# Sheet2.net
KiCad netlist of a schematic drawn in Altium Designer
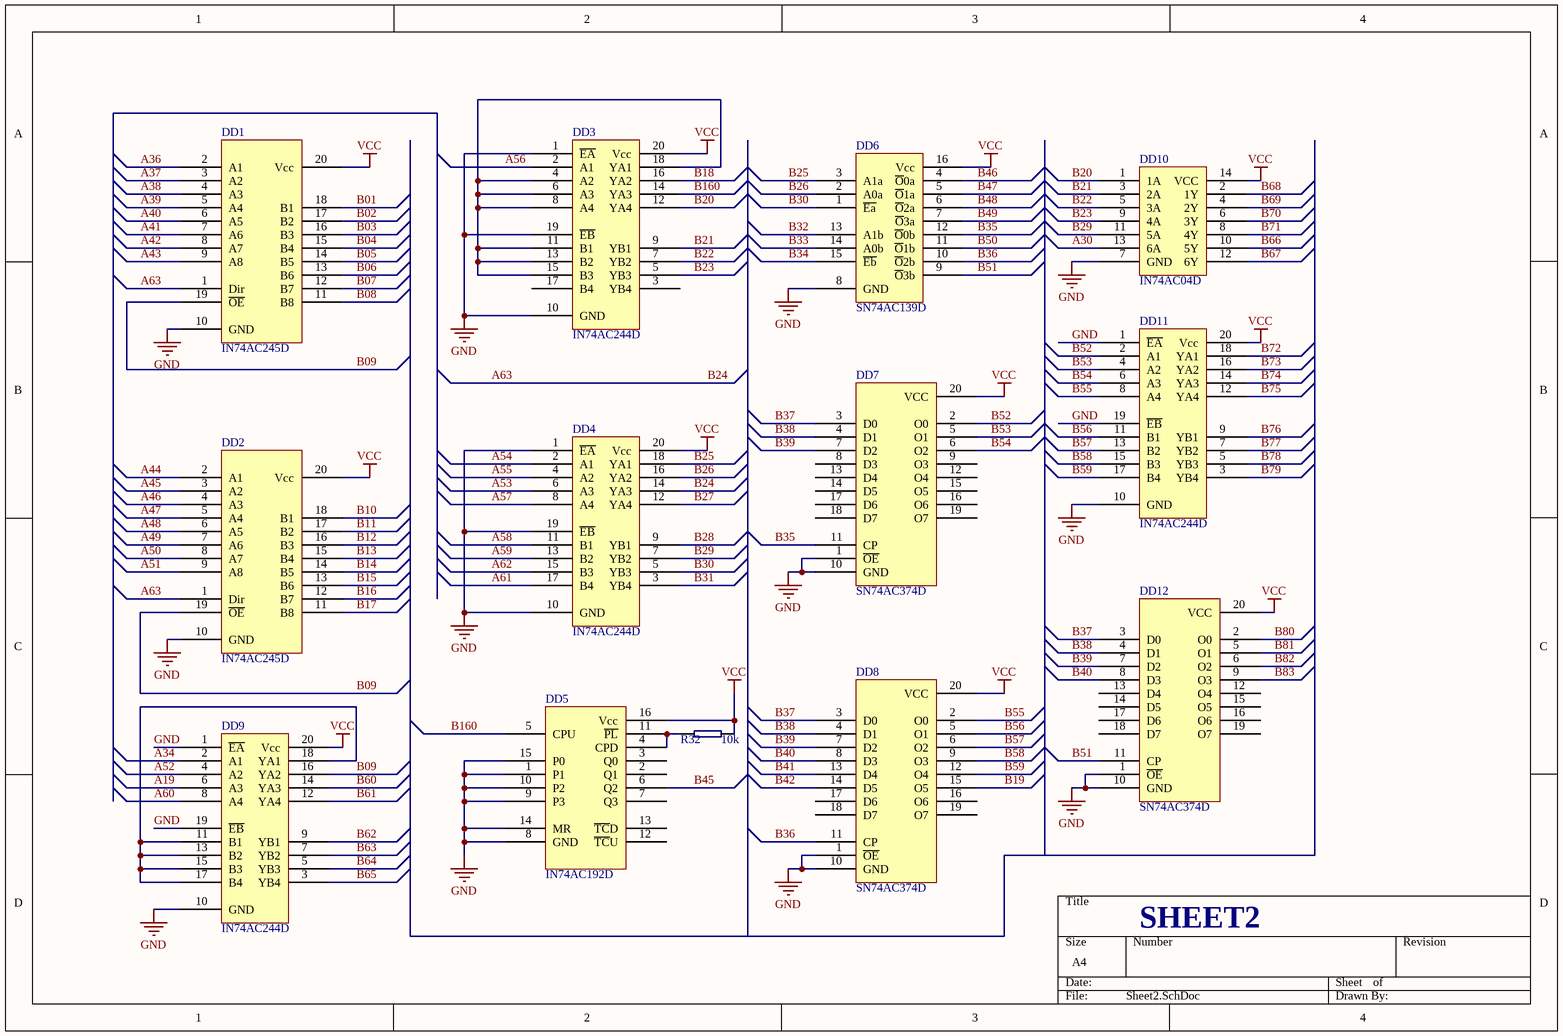
[diagram p0: Sheet2.SchDoc]

(export (version "E")
  (design (tool "Eeschema 10.0.6"))
  (components
    (comp (ref "DD1")
      (value "IN74AC245D")
      (footprint "20 SSOP-4.4")
      (libsource (lib "Board2") (part "IN74AC245D"))
    )
    (comp (ref "DD2")
      (value "IN74AC245D")
      (footprint "20 SSOP-4.4")
      (libsource (lib "Board2") (part "IN74AC245D"))
    )
    (comp (ref "DD3")
      (value "IN74AC244D")
      (footprint "20 SOIC-7.5")
      (libsource (lib "Board2") (part "IN74AC244D"))
    )
    (comp (ref "DD4")
      (value "IN74AC244D")
      (footprint "20 SOIC-7.5")
      (libsource (lib "Board2") (part "IN74AC244D"))
    )
    (comp (ref "DD5")
      (value "IN74AC192D")
      (footprint "16 SOIC-3.9")
      (libsource (lib "Board2") (part "IN74AC192D"))
    )
    (comp (ref "DD6")
      (value "SN74AC139D")
      (footprint "16 SOIC-3.9")
      (libsource (lib "Board2") (part "SN74AC139D"))
    )
    (comp (ref "DD7")
      (value "SN74AC374D")
      (footprint "20 SOIC-7.5")
      (libsource (lib "Board2") (part "SN74AC374D"))
    )
    (comp (ref "DD8")
      (value "SN74AC374D")
      (footprint "20 SOIC-7.5")
      (libsource (lib "Board2") (part "SN74AC374D"))
    )
    (comp (ref "DD9")
      (value "IN74AC244D")
      (footprint "20 SOIC-7.5")
      (libsource (lib "Board2") (part "IN74AC244D"))
    )
    (comp (ref "DD10")
      (value "IN74AC04D")
      (footprint "14 SOIC-3.9")
      (libsource (lib "Board2") (part "IN74AC04D"))
    )
    (comp (ref "DD11")
      (value "IN74AC244D")
      (footprint "20 SOIC-7.5")
      (libsource (lib "Board2") (part "IN74AC244D"))
    )
    (comp (ref "DD12")
      (value "SN74AC374D")
      (footprint "20 SOIC-7.5")
      (libsource (lib "*") (part "SN74AC374D"))
    )
    (comp (ref "R32")
      (value "10k")
      (footprint "0805")
      (fields (field (name "Comment") "R"))
      (libsource (lib "Board2") (part "R"))
    )
  )
  (nets
    (net (code "1") (name "/A19") (class "Default")
      (node (ref "DD9") (pin "6") (pinfunction "A3_6") (pintype "passive"))
    )
    (net (code "2") (name "/A30") (class "Default")
      (node (ref "DD10") (pin "13") (pinfunction "6A_13") (pintype "passive"))
    )
    (net (code "3") (name "/A34") (class "Default")
      (node (ref "DD9") (pin "2") (pinfunction "A1_2") (pintype "passive"))
    )
    (net (code "4") (name "/A36") (class "Default")
      (node (ref "DD1") (pin "2") (pinfunction "A1_2") (pintype "passive"))
    )
    (net (code "5") (name "/A37") (class "Default")
      (node (ref "DD1") (pin "3") (pinfunction "A2_3") (pintype "passive"))
    )
    (net (code "6") (name "/A38") (class "Default")
      (node (ref "DD1") (pin "4") (pinfunction "A3_4") (pintype "passive"))
    )
    (net (code "7") (name "/A39") (class "Default")
      (node (ref "DD1") (pin "5") (pinfunction "A4_5") (pintype "passive"))
    )
    (net (code "8") (name "/A40") (class "Default")
      (node (ref "DD1") (pin "6") (pinfunction "A5_6") (pintype "passive"))
    )
    (net (code "9") (name "/A41") (class "Default")
      (node (ref "DD1") (pin "7") (pinfunction "A6_7") (pintype "passive"))
    )
    (net (code "10") (name "/A42") (class "Default")
      (node (ref "DD1") (pin "8") (pinfunction "A7_8") (pintype "passive"))
    )
    (net (code "11") (name "/A43") (class "Default")
      (node (ref "DD1") (pin "9") (pinfunction "A8_9") (pintype "passive"))
    )
    (net (code "12") (name "/A44") (class "Default")
      (node (ref "DD2") (pin "2") (pinfunction "A1_2") (pintype "passive"))
    )
    (net (code "13") (name "/A45") (class "Default")
      (node (ref "DD2") (pin "3") (pinfunction "A2_3") (pintype "passive"))
    )
    (net (code "14") (name "/A46") (class "Default")
      (node (ref "DD2") (pin "4") (pinfunction "A3_4") (pintype "passive"))
    )
    (net (code "15") (name "/A47") (class "Default")
      (node (ref "DD2") (pin "5") (pinfunction "A4_5") (pintype "passive"))
    )
    (net (code "16") (name "/A48") (class "Default")
      (node (ref "DD2") (pin "6") (pinfunction "A5_6") (pintype "passive"))
    )
    (net (code "17") (name "/A49") (class "Default")
      (node (ref "DD2") (pin "7") (pinfunction "A6_7") (pintype "passive"))
    )
    (net (code "18") (name "/A50") (class "Default")
      (node (ref "DD2") (pin "8") (pinfunction "A7_8") (pintype "passive"))
    )
    (net (code "19") (name "/A51") (class "Default")
      (node (ref "DD2") (pin "9") (pinfunction "A8_9") (pintype "passive"))
    )
    (net (code "20") (name "/A52") (class "Default")
      (node (ref "DD9") (pin "4") (pinfunction "A2_4") (pintype "passive"))
    )
    (net (code "21") (name "/A53") (class "Default")
      (node (ref "DD4") (pin "6") (pinfunction "A3_6") (pintype "passive"))
    )
    (net (code "22") (name "/A54") (class "Default")
      (node (ref "DD4") (pin "2") (pinfunction "A1_2") (pintype "passive"))
    )
    (net (code "23") (name "/A55") (class "Default")
      (node (ref "DD4") (pin "4") (pinfunction "A2_4") (pintype "passive"))
    )
    (net (code "24") (name "/A56") (class "Default")
      (node (ref "DD3") (pin "2") (pinfunction "A1_2") (pintype "passive"))
    )
    (net (code "25") (name "/A57") (class "Default")
      (node (ref "DD4") (pin "8") (pinfunction "A4_8") (pintype "passive"))
    )
    (net (code "26") (name "/A58") (class "Default")
      (node (ref "DD4") (pin "11") (pinfunction "B1_11") (pintype "passive"))
    )
    (net (code "27") (name "/A59") (class "Default")
      (node (ref "DD4") (pin "13") (pinfunction "B2_13") (pintype "passive"))
    )
    (net (code "28") (name "/A60") (class "Default")
      (node (ref "DD9") (pin "8") (pinfunction "A4_8") (pintype "passive"))
    )
    (net (code "29") (name "/A61") (class "Default")
      (node (ref "DD4") (pin "17") (pinfunction "B4_17") (pintype "passive"))
    )
    (net (code "30") (name "/A62") (class "Default")
      (node (ref "DD4") (pin "15") (pinfunction "B3_15") (pintype "passive"))
    )
    (net (code "31") (name "/A63") (class "Default")
      (node (ref "DD1") (pin "1") (pinfunction "Dir_1") (pintype "passive"))
      (node (ref "DD2") (pin "1") (pinfunction "Dir_1") (pintype "passive"))
      (node (ref "DD4") (pin "14") (pinfunction "YA3_14") (pintype "passive"))
    )
    (net (code "32") (name "/B01") (class "Default")
      (node (ref "DD1") (pin "18") (pinfunction "B1_18") (pintype "passive"))
    )
    (net (code "33") (name "/B02") (class "Default")
      (node (ref "DD1") (pin "17") (pinfunction "B2_17") (pintype "passive"))
    )
    (net (code "34") (name "/B03") (class "Default")
      (node (ref "DD1") (pin "16") (pinfunction "B3_16") (pintype "passive"))
    )
    (net (code "35") (name "/B04") (class "Default")
      (node (ref "DD1") (pin "15") (pinfunction "B4_15") (pintype "passive"))
    )
    (net (code "36") (name "/B05") (class "Default")
      (node (ref "DD1") (pin "14") (pinfunction "B5_14") (pintype "passive"))
    )
    (net (code "37") (name "/B06") (class "Default")
      (node (ref "DD1") (pin "13") (pinfunction "B6_13") (pintype "passive"))
    )
    (net (code "38") (name "/B07") (class "Default")
      (node (ref "DD1") (pin "12") (pinfunction "B7_12") (pintype "passive"))
    )
    (net (code "39") (name "/B08") (class "Default")
      (node (ref "DD1") (pin "11") (pinfunction "B8_11") (pintype "passive"))
    )
    (net (code "40") (name "/B09") (class "Default")
      (node (ref "DD1") (pin "19") (pinfunction "~{OE}_19") (pintype "passive"))
      (node (ref "DD2") (pin "19") (pinfunction "~{OE}_19") (pintype "passive"))
      (node (ref "DD9") (pin "16") (pinfunction "YA2_16") (pintype "passive"))
    )
    (net (code "41") (name "/B10") (class "Default")
      (node (ref "DD2") (pin "18") (pinfunction "B1_18") (pintype "passive"))
    )
    (net (code "42") (name "/B11") (class "Default")
      (node (ref "DD2") (pin "17") (pinfunction "B2_17") (pintype "passive"))
    )
    (net (code "43") (name "/B12") (class "Default")
      (node (ref "DD2") (pin "16") (pinfunction "B3_16") (pintype "passive"))
    )
    (net (code "44") (name "/B13") (class "Default")
      (node (ref "DD2") (pin "15") (pinfunction "B4_15") (pintype "passive"))
    )
    (net (code "45") (name "/B14") (class "Default")
      (node (ref "DD2") (pin "14") (pinfunction "B5_14") (pintype "passive"))
    )
    (net (code "46") (name "/B15") (class "Default")
      (node (ref "DD2") (pin "13") (pinfunction "B6_13") (pintype "passive"))
    )
    (net (code "47") (name "/B16") (class "Default")
      (node (ref "DD2") (pin "12") (pinfunction "B7_12") (pintype "passive"))
    )
    (net (code "48") (name "/B17") (class "Default")
      (node (ref "DD2") (pin "11") (pinfunction "B8_11") (pintype "passive"))
    )
    (net (code "49") (name "/B18") (class "Default")
      (node (ref "DD3") (pin "16") (pinfunction "YA2_16") (pintype "passive"))
    )
    (net (code "50") (name "/B19") (class "Default")
      (node (ref "DD8") (pin "15") (pinfunction "O5_15") (pintype "passive"))
    )
    (net (code "51") (name "/B20") (class "Default")
      (node (ref "DD10") (pin "1") (pinfunction "1A_1") (pintype "passive"))
      (node (ref "DD3") (pin "12") (pinfunction "YA4_12") (pintype "passive"))
    )
    (net (code "52") (name "/B21") (class "Default")
      (node (ref "DD10") (pin "3") (pinfunction "2A_3") (pintype "passive"))
      (node (ref "DD3") (pin "9") (pinfunction "YB1_9") (pintype "passive"))
    )
    (net (code "53") (name "/B22") (class "Default")
      (node (ref "DD10") (pin "5") (pinfunction "3A_5") (pintype "passive"))
      (node (ref "DD3") (pin "7") (pinfunction "YB2_7") (pintype "passive"))
    )
    (net (code "54") (name "/B23") (class "Default")
      (node (ref "DD10") (pin "9") (pinfunction "4A_9") (pintype "passive"))
      (node (ref "DD3") (pin "5") (pinfunction "YB3_5") (pintype "passive"))
    )
    (net (code "55") (name "/B25") (class "Default")
      (node (ref "DD4") (pin "18") (pinfunction "YA1_18") (pintype "passive"))
      (node (ref "DD6") (pin "3") (pinfunction "A1a_3") (pintype "passive"))
    )
    (net (code "56") (name "/B26") (class "Default")
      (node (ref "DD4") (pin "16") (pinfunction "YA2_16") (pintype "passive"))
      (node (ref "DD6") (pin "2") (pinfunction "A0a_2") (pintype "passive"))
    )
    (net (code "57") (name "/B27") (class "Default")
      (node (ref "DD4") (pin "12") (pinfunction "YA4_12") (pintype "passive"))
    )
    (net (code "58") (name "/B28") (class "Default")
      (node (ref "DD4") (pin "9") (pinfunction "YB1_9") (pintype "passive"))
    )
    (net (code "59") (name "/B29") (class "Default")
      (node (ref "DD10") (pin "11") (pinfunction "5A_11") (pintype "passive"))
      (node (ref "DD4") (pin "7") (pinfunction "YB2_7") (pintype "passive"))
    )
    (net (code "60") (name "/B30") (class "Default")
      (node (ref "DD4") (pin "5") (pinfunction "YB3_5") (pintype "passive"))
      (node (ref "DD6") (pin "1") (pinfunction "~{Ea}_1") (pintype "passive"))
    )
    (net (code "61") (name "/B31") (class "Default")
      (node (ref "DD4") (pin "3") (pinfunction "YB4_3") (pintype "passive"))
    )
    (net (code "62") (name "/B32") (class "Default")
      (node (ref "DD6") (pin "13") (pinfunction "A1b_13") (pintype "passive"))
    )
    (net (code "63") (name "/B33") (class "Default")
      (node (ref "DD6") (pin "14") (pinfunction "A0b_14") (pintype "passive"))
    )
    (net (code "64") (name "/B34") (class "Default")
      (node (ref "DD6") (pin "15") (pinfunction "~{Eb}_15") (pintype "passive"))
    )
    (net (code "65") (name "/B35") (class "Default")
      (node (ref "DD6") (pin "12") (pinfunction "~{O}0b_12") (pintype "passive"))
      (node (ref "DD7") (pin "11") (pinfunction "CP_11") (pintype "passive"))
    )
    (net (code "66") (name "/B36") (class "Default")
      (node (ref "DD6") (pin "10") (pinfunction "~{O}2b_10") (pintype "passive"))
      (node (ref "DD8") (pin "11") (pinfunction "CP_11") (pintype "passive"))
    )
    (net (code "67") (name "/B37") (class "Default")
      (node (ref "DD12") (pin "3") (pinfunction "D0_3") (pintype "passive"))
      (node (ref "DD7") (pin "3") (pinfunction "D0_3") (pintype "passive"))
      (node (ref "DD8") (pin "3") (pinfunction "D0_3") (pintype "passive"))
    )
    (net (code "68") (name "/B38") (class "Default")
      (node (ref "DD12") (pin "4") (pinfunction "D1_4") (pintype "passive"))
      (node (ref "DD7") (pin "4") (pinfunction "D1_4") (pintype "passive"))
      (node (ref "DD8") (pin "4") (pinfunction "D1_4") (pintype "passive"))
    )
    (net (code "69") (name "/B39") (class "Default")
      (node (ref "DD12") (pin "7") (pinfunction "D2_7") (pintype "passive"))
      (node (ref "DD7") (pin "7") (pinfunction "D2_7") (pintype "passive"))
      (node (ref "DD8") (pin "7") (pinfunction "D2_7") (pintype "passive"))
    )
    (net (code "70") (name "/B40") (class "Default")
      (node (ref "DD12") (pin "8") (pinfunction "D3_8") (pintype "passive"))
      (node (ref "DD8") (pin "8") (pinfunction "D3_8") (pintype "passive"))
    )
    (net (code "71") (name "/B41") (class "Default")
      (node (ref "DD8") (pin "13") (pinfunction "D4_13") (pintype "passive"))
    )
    (net (code "72") (name "/B42") (class "Default")
      (node (ref "DD8") (pin "14") (pinfunction "D5_14") (pintype "passive"))
    )
    (net (code "73") (name "/B45") (class "Default")
      (node (ref "DD5") (pin "6") (pinfunction "Q2_6") (pintype "passive"))
    )
    (net (code "74") (name "/B46") (class "Default")
      (node (ref "DD6") (pin "4") (pinfunction "~{O}0a_4") (pintype "passive"))
    )
    (net (code "75") (name "/B47") (class "Default")
      (node (ref "DD6") (pin "5") (pinfunction "~{O}1a_5") (pintype "passive"))
    )
    (net (code "76") (name "/B48") (class "Default")
      (node (ref "DD6") (pin "6") (pinfunction "~{O}2a_6") (pintype "passive"))
    )
    (net (code "77") (name "/B49") (class "Default")
      (node (ref "DD6") (pin "7") (pinfunction "~{O}3a_7") (pintype "passive"))
    )
    (net (code "78") (name "/B50") (class "Default")
      (node (ref "DD6") (pin "11") (pinfunction "~{O}1b_11") (pintype "passive"))
    )
    (net (code "79") (name "/B51") (class "Default")
      (node (ref "DD12") (pin "11") (pinfunction "CP_11") (pintype "passive"))
      (node (ref "DD6") (pin "9") (pinfunction "~{O}3b_9") (pintype "passive"))
    )
    (net (code "80") (name "/B52") (class "Default")
      (node (ref "DD11") (pin "2") (pinfunction "A1_2") (pintype "passive"))
      (node (ref "DD7") (pin "2") (pinfunction "O0_2") (pintype "passive"))
    )
    (net (code "81") (name "/B53") (class "Default")
      (node (ref "DD11") (pin "4") (pinfunction "A2_4") (pintype "passive"))
      (node (ref "DD7") (pin "5") (pinfunction "O1_5") (pintype "passive"))
    )
    (net (code "82") (name "/B54") (class "Default")
      (node (ref "DD11") (pin "6") (pinfunction "A3_6") (pintype "passive"))
      (node (ref "DD7") (pin "6") (pinfunction "O2_6") (pintype "passive"))
    )
    (net (code "83") (name "/B55") (class "Default")
      (node (ref "DD11") (pin "8") (pinfunction "A4_8") (pintype "passive"))
      (node (ref "DD8") (pin "2") (pinfunction "O0_2") (pintype "passive"))
    )
    (net (code "84") (name "/B56") (class "Default")
      (node (ref "DD11") (pin "11") (pinfunction "B1_11") (pintype "passive"))
      (node (ref "DD8") (pin "5") (pinfunction "O1_5") (pintype "passive"))
    )
    (net (code "85") (name "/B57") (class "Default")
      (node (ref "DD11") (pin "13") (pinfunction "B2_13") (pintype "passive"))
      (node (ref "DD8") (pin "6") (pinfunction "O2_6") (pintype "passive"))
    )
    (net (code "86") (name "/B58") (class "Default")
      (node (ref "DD11") (pin "15") (pinfunction "B3_15") (pintype "passive"))
      (node (ref "DD8") (pin "9") (pinfunction "O3_9") (pintype "passive"))
    )
    (net (code "87") (name "/B59") (class "Default")
      (node (ref "DD11") (pin "17") (pinfunction "B4_17") (pintype "passive"))
      (node (ref "DD8") (pin "12") (pinfunction "O4_12") (pintype "passive"))
    )
    (net (code "88") (name "/B60") (class "Default")
      (node (ref "DD9") (pin "14") (pinfunction "YA3_14") (pintype "passive"))
    )
    (net (code "89") (name "/B61") (class "Default")
      (node (ref "DD9") (pin "12") (pinfunction "YA4_12") (pintype "passive"))
    )
    (net (code "90") (name "/B62") (class "Default")
      (node (ref "DD9") (pin "9") (pinfunction "YB1_9") (pintype "passive"))
    )
    (net (code "91") (name "/B63") (class "Default")
      (node (ref "DD9") (pin "7") (pinfunction "YB2_7") (pintype "passive"))
    )
    (net (code "92") (name "/B64") (class "Default")
      (node (ref "DD9") (pin "5") (pinfunction "YB3_5") (pintype "passive"))
    )
    (net (code "93") (name "/B65") (class "Default")
      (node (ref "DD9") (pin "3") (pinfunction "YB4_3") (pintype "passive"))
    )
    (net (code "94") (name "/B66") (class "Default")
      (node (ref "DD10") (pin "10") (pinfunction "5Y_10") (pintype "passive"))
    )
    (net (code "95") (name "/B67") (class "Default")
      (node (ref "DD10") (pin "12") (pinfunction "6Y_12") (pintype "passive"))
    )
    (net (code "96") (name "/B68") (class "Default")
      (node (ref "DD10") (pin "2") (pinfunction "1Y_2") (pintype "passive"))
    )
    (net (code "97") (name "/B69") (class "Default")
      (node (ref "DD10") (pin "4") (pinfunction "2Y_4") (pintype "passive"))
    )
    (net (code "98") (name "/B70") (class "Default")
      (node (ref "DD10") (pin "6") (pinfunction "3Y_6") (pintype "passive"))
    )
    (net (code "99") (name "/B71") (class "Default")
      (node (ref "DD10") (pin "8") (pinfunction "4Y_8") (pintype "passive"))
    )
    (net (code "100") (name "/B72") (class "Default")
      (node (ref "DD11") (pin "18") (pinfunction "YA1_18") (pintype "passive"))
    )
    (net (code "101") (name "/B73") (class "Default")
      (node (ref "DD11") (pin "16") (pinfunction "YA2_16") (pintype "passive"))
    )
    (net (code "102") (name "/B74") (class "Default")
      (node (ref "DD11") (pin "14") (pinfunction "YA3_14") (pintype "passive"))
    )
    (net (code "103") (name "/B75") (class "Default")
      (node (ref "DD11") (pin "12") (pinfunction "YA4_12") (pintype "passive"))
    )
    (net (code "104") (name "/B76") (class "Default")
      (node (ref "DD11") (pin "9") (pinfunction "YB1_9") (pintype "passive"))
    )
    (net (code "105") (name "/B77") (class "Default")
      (node (ref "DD11") (pin "7") (pinfunction "YB2_7") (pintype "passive"))
    )
    (net (code "106") (name "/B78") (class "Default")
      (node (ref "DD11") (pin "5") (pinfunction "YB3_5") (pintype "passive"))
    )
    (net (code "107") (name "/B79") (class "Default")
      (node (ref "DD11") (pin "3") (pinfunction "YB4_3") (pintype "passive"))
    )
    (net (code "108") (name "/B80") (class "Default")
      (node (ref "DD12") (pin "2") (pinfunction "O0_2") (pintype "passive"))
    )
    (net (code "109") (name "/B81") (class "Default")
      (node (ref "DD12") (pin "5") (pinfunction "O1_5") (pintype "passive"))
    )
    (net (code "110") (name "/B82") (class "Default")
      (node (ref "DD12") (pin "6") (pinfunction "O2_6") (pintype "passive"))
    )
    (net (code "111") (name "/B83") (class "Default")
      (node (ref "DD12") (pin "9") (pinfunction "O3_9") (pintype "passive"))
    )
    (net (code "112") (name "/B160") (class "Default")
      (node (ref "DD3") (pin "14") (pinfunction "YA3_14") (pintype "passive"))
      (node (ref "DD5") (pin "5") (pinfunction "CPU_5") (pintype "passive"))
    )
    (net (code "113") (name "GND") (class "Default")
      (node (ref "DD1") (pin "10") (pinfunction "GND_10") (pintype "passive"))
      (node (ref "DD10") (pin "7") (pinfunction "GND_7") (pintype "passive"))
      (node (ref "DD11") (pin "1") (pinfunction "~{EA}_1") (pintype "passive"))
      (node (ref "DD11") (pin "10") (pinfunction "GND_10") (pintype "passive"))
      (node (ref "DD11") (pin "19") (pinfunction "~{EB}_19") (pintype "passive"))
      (node (ref "DD12") (pin "1") (pinfunction "~{OE}_1") (pintype "passive"))
      (node (ref "DD12") (pin "10") (pinfunction "GND_10") (pintype "passive"))
      (node (ref "DD2") (pin "10") (pinfunction "GND_10") (pintype "passive"))
      (node (ref "DD3") (pin "1") (pinfunction "~{EA}_1") (pintype "passive"))
      (node (ref "DD3") (pin "10") (pinfunction "GND_10") (pintype "passive"))
      (node (ref "DD3") (pin "19") (pinfunction "~{EB}_19") (pintype "passive"))
      (node (ref "DD4") (pin "1") (pinfunction "~{EA}_1") (pintype "passive"))
      (node (ref "DD4") (pin "10") (pinfunction "GND_10") (pintype "passive"))
      (node (ref "DD4") (pin "19") (pinfunction "~{EB}_19") (pintype "passive"))
      (node (ref "DD5") (pin "1") (pinfunction "P1_1") (pintype "passive"))
      (node (ref "DD5") (pin "10") (pinfunction "P2_10") (pintype "passive"))
      (node (ref "DD5") (pin "14") (pinfunction "MR_14") (pintype "passive"))
      (node (ref "DD5") (pin "15") (pinfunction "P0_15") (pintype "passive"))
      (node (ref "DD5") (pin "8") (pinfunction "GND_8") (pintype "passive"))
      (node (ref "DD5") (pin "9") (pinfunction "P3_9") (pintype "passive"))
      (node (ref "DD6") (pin "8") (pinfunction "GND_8") (pintype "passive"))
      (node (ref "DD7") (pin "1") (pinfunction "~{OE}_1") (pintype "passive"))
      (node (ref "DD7") (pin "10") (pinfunction "GND_10") (pintype "passive"))
      (node (ref "DD8") (pin "1") (pinfunction "~{OE}_1") (pintype "passive"))
      (node (ref "DD8") (pin "10") (pinfunction "GND_10") (pintype "passive"))
      (node (ref "DD9") (pin "1") (pinfunction "~{EA}_1") (pintype "passive"))
      (node (ref "DD9") (pin "10") (pinfunction "GND_10") (pintype "passive"))
      (node (ref "DD9") (pin "19") (pinfunction "~{EB}_19") (pintype "passive"))
    )
    (net (code "114") (name "Net-(DD3-A2)") (class "Default")
      (node (ref "DD3") (pin "11") (pinfunction "B1_11") (pintype "passive"))
      (node (ref "DD3") (pin "13") (pinfunction "B2_13") (pintype "passive"))
      (node (ref "DD3") (pin "15") (pinfunction "B3_15") (pintype "passive"))
      (node (ref "DD3") (pin "18") (pinfunction "YA1_18") (pintype "passive"))
      (node (ref "DD3") (pin "4") (pinfunction "A2_4") (pintype "passive"))
      (node (ref "DD3") (pin "6") (pinfunction "A3_6") (pintype "passive"))
      (node (ref "DD3") (pin "8") (pinfunction "A4_8") (pintype "passive"))
    )
    (net (code "115") (name "Net-(DD5-CPD)") (class "Default")
      (node (ref "DD5") (pin "11") (pinfunction "~{PL}_11") (pintype "passive"))
      (node (ref "DD5") (pin "4") (pinfunction "CPD_4") (pintype "passive"))
      (node (ref "R32") (pin "1") (pinfunction "1_1") (pintype "passive"))
    )
    (net (code "116") (name "Net-(DD9-B1)") (class "Default")
      (node (ref "DD9") (pin "11") (pinfunction "B1_11") (pintype "passive"))
      (node (ref "DD9") (pin "13") (pinfunction "B2_13") (pintype "passive"))
      (node (ref "DD9") (pin "15") (pinfunction "B3_15") (pintype "passive"))
      (node (ref "DD9") (pin "17") (pinfunction "B4_17") (pintype "passive"))
      (node (ref "DD9") (pin "18") (pinfunction "YA1_18") (pintype "passive"))
    )
    (net (code "117") (name "VCC") (class "Default")
      (node (ref "DD1") (pin "20") (pinfunction "Vcc_20") (pintype "passive"))
      (node (ref "DD10") (pin "14") (pinfunction "VCC_14") (pintype "passive"))
      (node (ref "DD11") (pin "20") (pinfunction "Vcc_20") (pintype "passive"))
      (node (ref "DD12") (pin "20") (pinfunction "VCC_20") (pintype "passive"))
      (node (ref "DD2") (pin "20") (pinfunction "Vcc_20") (pintype "passive"))
      (node (ref "DD3") (pin "20") (pinfunction "Vcc_20") (pintype "passive"))
      (node (ref "DD4") (pin "20") (pinfunction "Vcc_20") (pintype "passive"))
      (node (ref "DD5") (pin "16") (pinfunction "Vcc_16") (pintype "passive"))
      (node (ref "DD6") (pin "16") (pinfunction "Vcc_16") (pintype "passive"))
      (node (ref "DD7") (pin "20") (pinfunction "VCC_20") (pintype "passive"))
      (node (ref "DD8") (pin "20") (pinfunction "VCC_20") (pintype "passive"))
      (node (ref "DD9") (pin "20") (pinfunction "Vcc_20") (pintype "passive"))
      (node (ref "R32") (pin "2") (pinfunction "0_2") (pintype "passive"))
    )
    (net (code "118") (name "unconnected-(DD3-B4-Pad17)") (class "Default")
      (node (ref "DD3") (pin "17") (pinfunction "B4_17") (pintype "passive"))
    )
    (net (code "119") (name "unconnected-(DD3-YB4-Pad3)") (class "Default")
      (node (ref "DD3") (pin "3") (pinfunction "YB4_3") (pintype "passive"))
    )
    (net (code "120") (name "unconnected-(DD5-Q0-Pad3)") (class "Default")
      (node (ref "DD5") (pin "3") (pinfunction "Q0_3") (pintype "passive"))
    )
    (net (code "121") (name "unconnected-(DD5-Q1-Pad2)") (class "Default")
      (node (ref "DD5") (pin "2") (pinfunction "Q1_2") (pintype "passive"))
    )
    (net (code "122") (name "unconnected-(DD5-Q3-Pad7)") (class "Default")
      (node (ref "DD5") (pin "7") (pinfunction "Q3_7") (pintype "passive"))
    )
    (net (code "123") (name "unconnected-(DD5-~{TC}D-Pad13)") (class "Default")
      (node (ref "DD5") (pin "13") (pinfunction "~{TC}D_13") (pintype "passive"))
    )
    (net (code "124") (name "unconnected-(DD5-~{TC}U-Pad12)") (class "Default")
      (node (ref "DD5") (pin "12") (pinfunction "~{TC}U_12") (pintype "passive"))
    )
    (net (code "125") (name "unconnected-(DD7-D3-Pad8)") (class "Default")
      (node (ref "DD7") (pin "8") (pinfunction "D3_8") (pintype "passive"))
    )
    (net (code "126") (name "unconnected-(DD7-D4-Pad13)") (class "Default")
      (node (ref "DD7") (pin "13") (pinfunction "D4_13") (pintype "passive"))
    )
    (net (code "127") (name "unconnected-(DD7-D5-Pad14)") (class "Default")
      (node (ref "DD7") (pin "14") (pinfunction "D5_14") (pintype "passive"))
    )
    (net (code "128") (name "unconnected-(DD7-D6-Pad17)") (class "Default")
      (node (ref "DD7") (pin "17") (pinfunction "D6_17") (pintype "passive"))
    )
    (net (code "129") (name "unconnected-(DD7-D7-Pad18)") (class "Default")
      (node (ref "DD7") (pin "18") (pinfunction "D7_18") (pintype "passive"))
    )
    (net (code "130") (name "unconnected-(DD7-O3-Pad9)") (class "Default")
      (node (ref "DD7") (pin "9") (pinfunction "O3_9") (pintype "passive"))
    )
    (net (code "131") (name "unconnected-(DD7-O4-Pad12)") (class "Default")
      (node (ref "DD7") (pin "12") (pinfunction "O4_12") (pintype "passive"))
    )
    (net (code "132") (name "unconnected-(DD7-O5-Pad15)") (class "Default")
      (node (ref "DD7") (pin "15") (pinfunction "O5_15") (pintype "passive"))
    )
    (net (code "133") (name "unconnected-(DD7-O6-Pad16)") (class "Default")
      (node (ref "DD7") (pin "16") (pinfunction "O6_16") (pintype "passive"))
    )
    (net (code "134") (name "unconnected-(DD7-O7-Pad19)") (class "Default")
      (node (ref "DD7") (pin "19") (pinfunction "O7_19") (pintype "passive"))
    )
    (net (code "135") (name "unconnected-(DD8-D6-Pad17)") (class "Default")
      (node (ref "DD8") (pin "17") (pinfunction "D6_17") (pintype "passive"))
    )
    (net (code "136") (name "unconnected-(DD8-D7-Pad18)") (class "Default")
      (node (ref "DD8") (pin "18") (pinfunction "D7_18") (pintype "passive"))
    )
    (net (code "137") (name "unconnected-(DD8-O6-Pad16)") (class "Default")
      (node (ref "DD8") (pin "16") (pinfunction "O6_16") (pintype "passive"))
    )
    (net (code "138") (name "unconnected-(DD8-O7-Pad19)") (class "Default")
      (node (ref "DD8") (pin "19") (pinfunction "O7_19") (pintype "passive"))
    )
    (net (code "139") (name "unconnected-(DD12-D4-Pad13)") (class "Default")
      (node (ref "DD12") (pin "13") (pinfunction "D4_13") (pintype "passive"))
    )
    (net (code "140") (name "unconnected-(DD12-D5-Pad14)") (class "Default")
      (node (ref "DD12") (pin "14") (pinfunction "D5_14") (pintype "passive"))
    )
    (net (code "141") (name "unconnected-(DD12-D6-Pad17)") (class "Default")
      (node (ref "DD12") (pin "17") (pinfunction "D6_17") (pintype "passive"))
    )
    (net (code "142") (name "unconnected-(DD12-D7-Pad18)") (class "Default")
      (node (ref "DD12") (pin "18") (pinfunction "D7_18") (pintype "passive"))
    )
    (net (code "143") (name "unconnected-(DD12-O4-Pad12)") (class "Default")
      (node (ref "DD12") (pin "12") (pinfunction "O4_12") (pintype "passive"))
    )
    (net (code "144") (name "unconnected-(DD12-O5-Pad15)") (class "Default")
      (node (ref "DD12") (pin "15") (pinfunction "O5_15") (pintype "passive"))
    )
    (net (code "145") (name "unconnected-(DD12-O6-Pad16)") (class "Default")
      (node (ref "DD12") (pin "16") (pinfunction "O6_16") (pintype "passive"))
    )
    (net (code "146") (name "unconnected-(DD12-O7-Pad19)") (class "Default")
      (node (ref "DD12") (pin "19") (pinfunction "O7_19") (pintype "passive"))
    )
  )
)
